# hub75d.net
KiCad netlist of a schematic drawn in Altium Designer
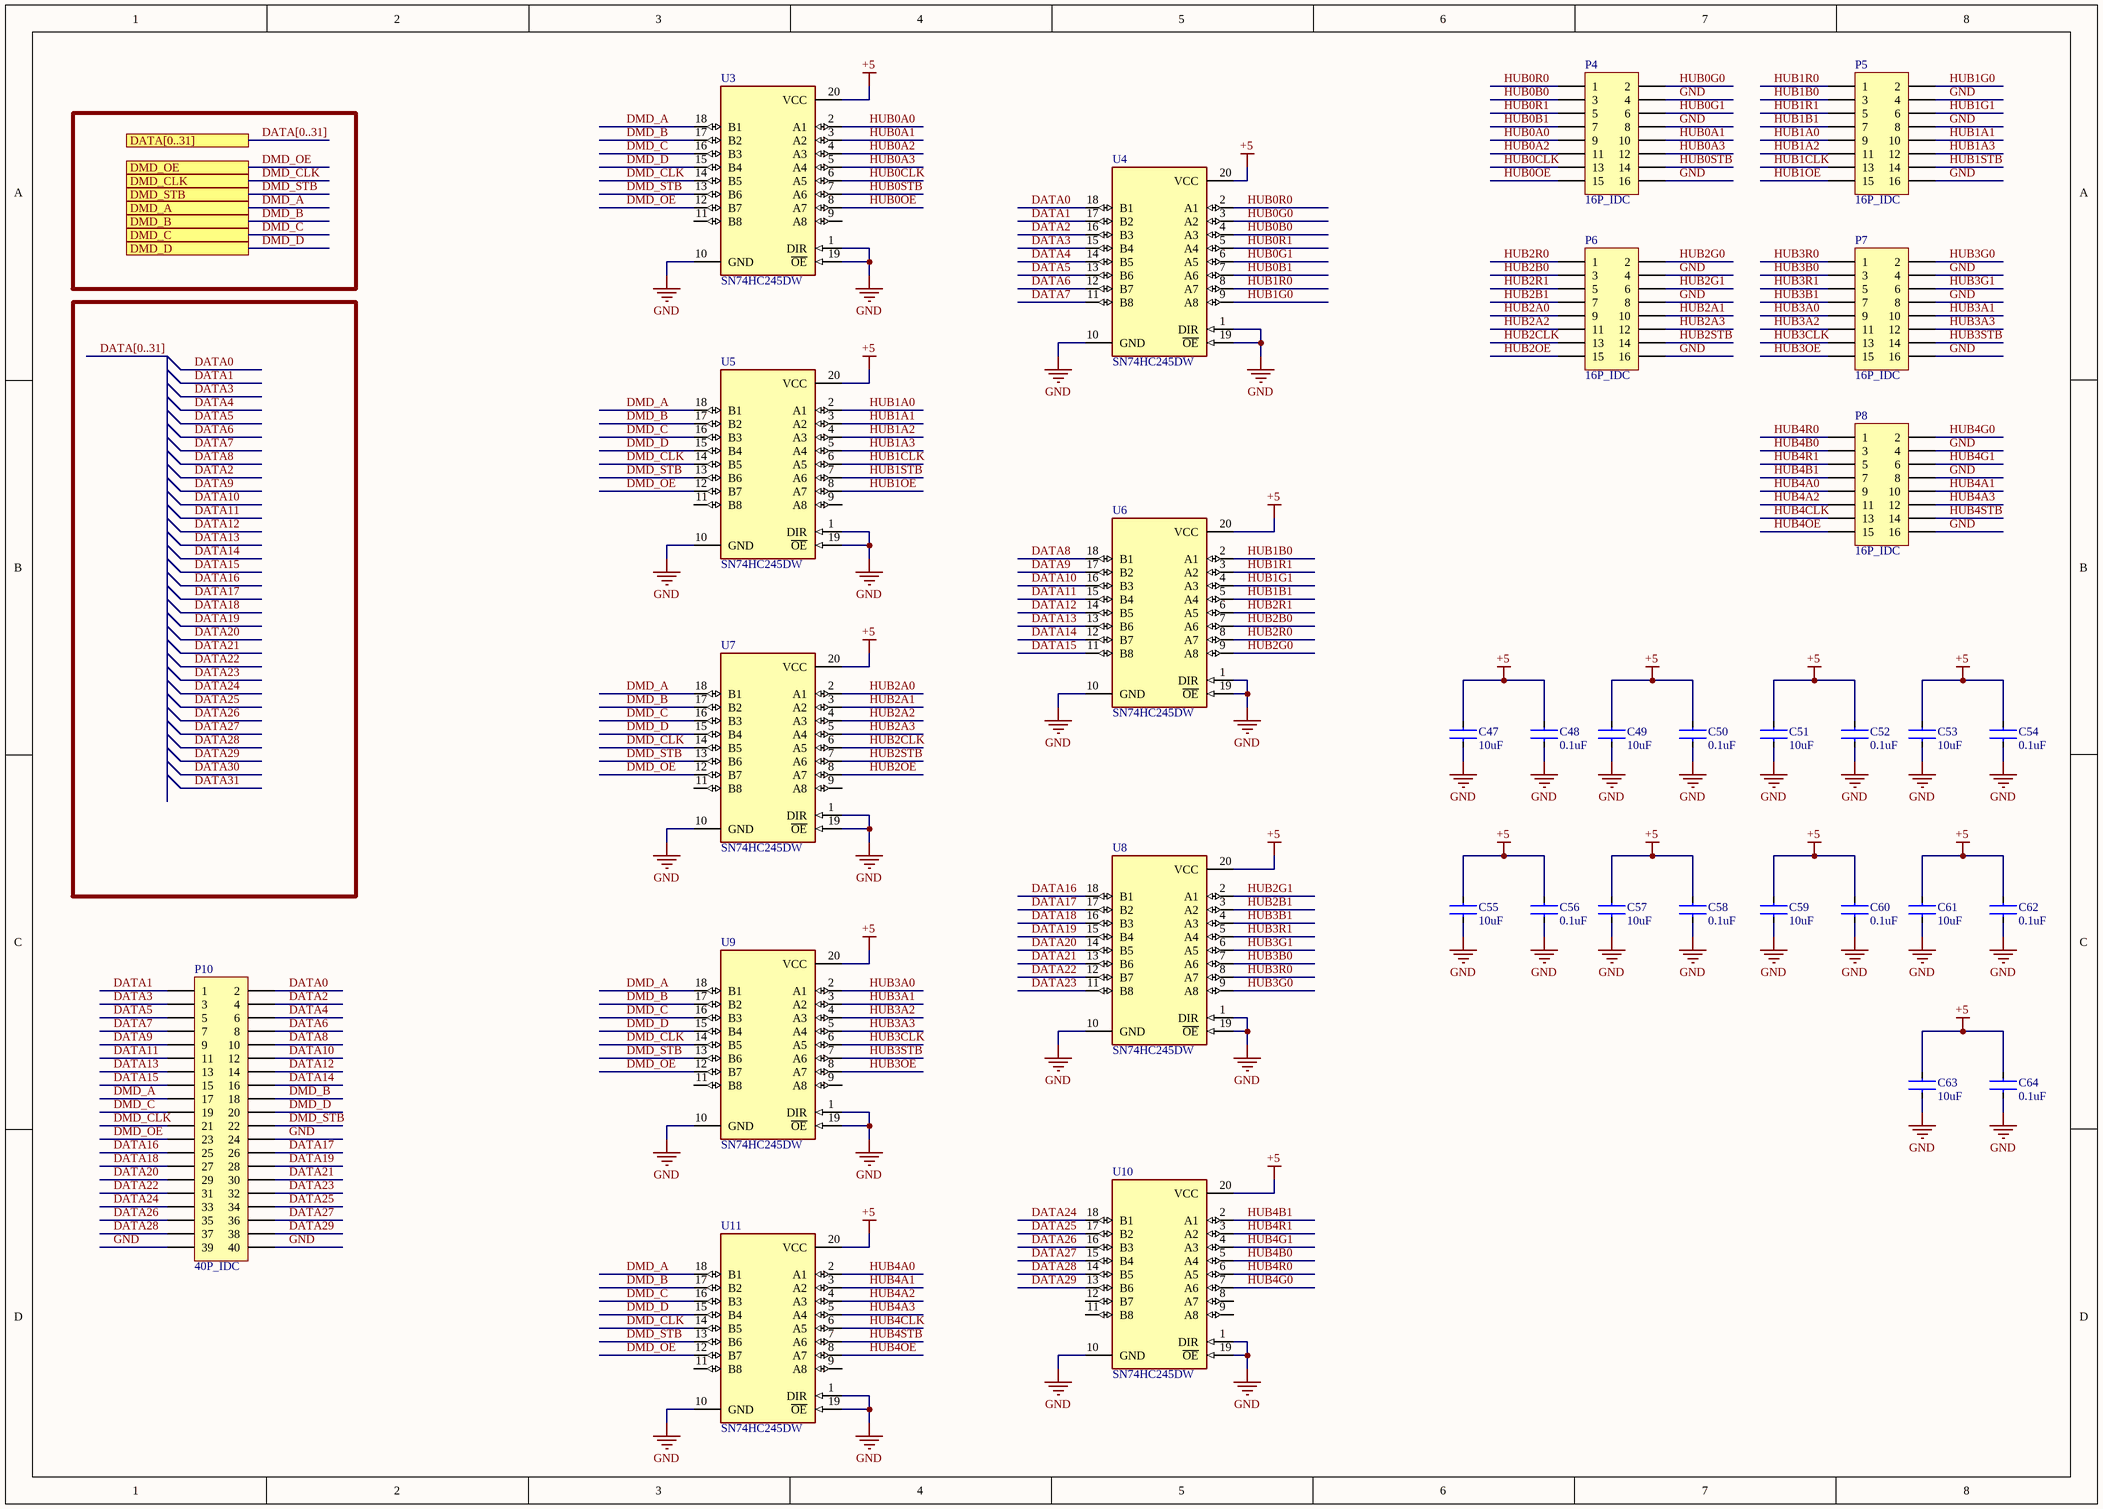
[diagram p0: hub75d.SchDoc]

(export (version "E")
  (design (tool "Eeschema 10.0.6"))
  (components
    (comp (ref "C47")
      (value "10uF")
      (footprint "C0402")
      (description "Cap Ceramic 10uF 16V X7R 10% Pad SMD 1206 125°C T/R")
      (fields
        (field (name "MANUFACTURER") "Samsung")
        (field (name "MANUFACTURER PART NUMBER") "CL31B106KOHNNNE")
      )
      (libsource (lib "afra") (part "CL31B106KOHNNNE"))
    )
    (comp (ref "C48")
      (value "0.1uF")
      (footprint "C0402")
      (description "Ceramic capacitor SMD-1206 100nF /50V X7R# K +-10%, Samsung, RoHS")
      (fields
        (field (name "MANUFACTURER") "Samsung")
        (field (name "MANUFACTURER PART NUMBER") "CL31B104KBCNNNC")
      )
      (libsource (lib "afra") (part "CL31B104KBCNNNC"))
    )
    (comp (ref "C49")
      (value "10uF")
      (footprint "C0402")
      (description "Cap Ceramic 10uF 16V X7R 10% Pad SMD 1206 125°C T/R")
      (fields
        (field (name "MANUFACTURER") "Samsung")
        (field (name "MANUFACTURER PART NUMBER") "CL31B106KOHNNNE")
      )
      (libsource (lib "afra") (part "CL31B106KOHNNNE"))
    )
    (comp (ref "C50")
      (value "0.1uF")
      (footprint "C0402")
      (description "Ceramic capacitor SMD-1206 100nF /50V X7R# K +-10%, Samsung, RoHS")
      (fields
        (field (name "MANUFACTURER") "Samsung")
        (field (name "MANUFACTURER PART NUMBER") "CL31B104KBCNNNC")
      )
      (libsource (lib "afra") (part "CL31B104KBCNNNC"))
    )
    (comp (ref "C51")
      (value "10uF")
      (footprint "C0402")
      (description "Cap Ceramic 10uF 16V X7R 10% Pad SMD 1206 125°C T/R")
      (fields
        (field (name "MANUFACTURER") "Samsung")
        (field (name "MANUFACTURER PART NUMBER") "CL31B106KOHNNNE")
      )
      (libsource (lib "afra") (part "CL31B106KOHNNNE"))
    )
    (comp (ref "C52")
      (value "0.1uF")
      (footprint "C0402")
      (description "Ceramic capacitor SMD-1206 100nF /50V X7R# K +-10%, Samsung, RoHS")
      (fields
        (field (name "MANUFACTURER") "Samsung")
        (field (name "MANUFACTURER PART NUMBER") "CL31B104KBCNNNC")
      )
      (libsource (lib "afra") (part "CL31B104KBCNNNC"))
    )
    (comp (ref "C53")
      (value "10uF")
      (footprint "C0402")
      (description "Cap Ceramic 10uF 16V X7R 10% Pad SMD 1206 125°C T/R")
      (fields
        (field (name "MANUFACTURER") "Samsung")
        (field (name "MANUFACTURER PART NUMBER") "CL31B106KOHNNNE")
      )
      (libsource (lib "afra") (part "CL31B106KOHNNNE"))
    )
    (comp (ref "C54")
      (value "0.1uF")
      (footprint "C0402")
      (description "Ceramic capacitor SMD-1206 100nF /50V X7R# K +-10%, Samsung, RoHS")
      (fields
        (field (name "MANUFACTURER") "Samsung")
        (field (name "MANUFACTURER PART NUMBER") "CL31B104KBCNNNC")
      )
      (libsource (lib "afra") (part "CL31B104KBCNNNC"))
    )
    (comp (ref "C55")
      (value "10uF")
      (footprint "C0402")
      (description "Cap Ceramic 10uF 16V X7R 10% Pad SMD 1206 125°C T/R")
      (fields
        (field (name "MANUFACTURER") "Samsung")
        (field (name "MANUFACTURER PART NUMBER") "CL31B106KOHNNNE")
      )
      (libsource (lib "afra") (part "CL31B106KOHNNNE"))
    )
    (comp (ref "C56")
      (value "0.1uF")
      (footprint "C0402")
      (description "Ceramic capacitor SMD-1206 100nF /50V X7R# K +-10%, Samsung, RoHS")
      (fields
        (field (name "MANUFACTURER") "Samsung")
        (field (name "MANUFACTURER PART NUMBER") "CL31B104KBCNNNC")
      )
      (libsource (lib "afra") (part "CL31B104KBCNNNC"))
    )
    (comp (ref "C57")
      (value "10uF")
      (footprint "C0402")
      (description "Cap Ceramic 10uF 16V X7R 10% Pad SMD 1206 125°C T/R")
      (fields
        (field (name "MANUFACTURER") "Samsung")
        (field (name "MANUFACTURER PART NUMBER") "CL31B106KOHNNNE")
      )
      (libsource (lib "afra") (part "CL31B106KOHNNNE"))
    )
    (comp (ref "C58")
      (value "0.1uF")
      (footprint "C0402")
      (description "Ceramic capacitor SMD-1206 100nF /50V X7R# K +-10%, Samsung, RoHS")
      (fields
        (field (name "MANUFACTURER") "Samsung")
        (field (name "MANUFACTURER PART NUMBER") "CL31B104KBCNNNC")
      )
      (libsource (lib "afra") (part "CL31B104KBCNNNC"))
    )
    (comp (ref "C59")
      (value "10uF")
      (footprint "C0402")
      (description "Cap Ceramic 10uF 16V X7R 10% Pad SMD 1206 125°C T/R")
      (fields
        (field (name "MANUFACTURER") "Samsung")
        (field (name "MANUFACTURER PART NUMBER") "CL31B106KOHNNNE")
      )
      (libsource (lib "afra") (part "CL31B106KOHNNNE"))
    )
    (comp (ref "C60")
      (value "0.1uF")
      (footprint "C0402")
      (description "Ceramic capacitor SMD-1206 100nF /50V X7R# K +-10%, Samsung, RoHS")
      (fields
        (field (name "MANUFACTURER") "Samsung")
        (field (name "MANUFACTURER PART NUMBER") "CL31B104KBCNNNC")
      )
      (libsource (lib "afra") (part "CL31B104KBCNNNC"))
    )
    (comp (ref "C61")
      (value "10uF")
      (footprint "C0402")
      (description "Cap Ceramic 10uF 16V X7R 10% Pad SMD 1206 125°C T/R")
      (fields
        (field (name "MANUFACTURER") "Samsung")
        (field (name "MANUFACTURER PART NUMBER") "CL31B106KOHNNNE")
      )
      (libsource (lib "afra") (part "CL31B106KOHNNNE"))
    )
    (comp (ref "C62")
      (value "0.1uF")
      (footprint "C0402")
      (description "Ceramic capacitor SMD-1206 100nF /50V X7R# K +-10%, Samsung, RoHS")
      (fields
        (field (name "MANUFACTURER") "Samsung")
        (field (name "MANUFACTURER PART NUMBER") "CL31B104KBCNNNC")
      )
      (libsource (lib "afra") (part "CL31B104KBCNNNC"))
    )
    (comp (ref "C63")
      (value "10uF")
      (footprint "C0402")
      (description "Cap Ceramic 10uF 16V X7R 10% Pad SMD 1206 125°C T/R")
      (fields
        (field (name "MANUFACTURER") "Samsung")
        (field (name "MANUFACTURER PART NUMBER") "CL31B106KOHNNNE")
      )
      (libsource (lib "afra") (part "CL31B106KOHNNNE"))
    )
    (comp (ref "C64")
      (value "0.1uF")
      (footprint "C0402")
      (description "Ceramic capacitor SMD-1206 100nF /50V X7R# K +-10%, Samsung, RoHS")
      (fields
        (field (name "MANUFACTURER") "Samsung")
        (field (name "MANUFACTURER PART NUMBER") "CL31B104KBCNNNC")
      )
      (libsource (lib "afra") (part "CL31B104KBCNNNC"))
    )
    (comp (ref "P4")
      (value "16P_IDC")
      (footprint "16Pin_IDC_Connector")
      (description "Headers & Wire Housings 16P STRAIGHT")
      (fields
        (field (name "MANUFACTURER") "Adam Equipment")
        (field (name "MANUFACTURER PART NUMBER") "BHR-16-VUA")
      )
      (libsource (lib "afra") (part "BHR-16-VUA"))
    )
    (comp (ref "P5")
      (value "16P_IDC")
      (footprint "16Pin_IDC_Connector")
      (description "Headers & Wire Housings 16P STRAIGHT")
      (fields
        (field (name "MANUFACTURER") "Adam Equipment")
        (field (name "MANUFACTURER PART NUMBER") "BHR-16-VUA")
      )
      (libsource (lib "afra") (part "BHR-16-VUA"))
    )
    (comp (ref "P6")
      (value "16P_IDC")
      (footprint "16Pin_IDC_Connector")
      (description "Headers & Wire Housings 16P STRAIGHT")
      (fields
        (field (name "MANUFACTURER") "Adam Equipment")
        (field (name "MANUFACTURER PART NUMBER") "BHR-16-VUA")
      )
      (libsource (lib "afra") (part "BHR-16-VUA"))
    )
    (comp (ref "P7")
      (value "16P_IDC")
      (footprint "16Pin_IDC_Connector")
      (description "Headers & Wire Housings 16P STRAIGHT")
      (fields
        (field (name "MANUFACTURER") "Adam Equipment")
        (field (name "MANUFACTURER PART NUMBER") "BHR-16-VUA")
      )
      (libsource (lib "afra") (part "BHR-16-VUA"))
    )
    (comp (ref "P8")
      (value "16P_IDC")
      (footprint "16Pin_IDC_Connector")
      (description "Headers & Wire Housings 16P STRAIGHT")
      (fields
        (field (name "MANUFACTURER") "Adam Equipment")
        (field (name "MANUFACTURER PART NUMBER") "BHR-16-VUA")
      )
      (libsource (lib "afra") (part "BHR-16-VUA"))
    )
    (comp (ref "P10")
      (value "40P_IDC")
      (footprint "40Pin_IDC_Connector")
      (description "Conn Shrouded Header (4 Sides) HDR 40 POS 2.54mm Solder ST Top Entry Thru-Hole Tray")
      (fields
        (field (name "MANUFACTURER") "Adam Equipment")
        (field (name "MANUFACTURER PART NUMBER") "BHR-20-VUA")
      )
      (libsource (lib "afra") (part "BHR-40-VUA"))
    )
    (comp (ref "U3")
      (value "SN74HC245DW")
      (footprint "DB20")
      (description "Transceiver, Non-Inverting 1 Element 8 Bit per Element Push-Pull Output 20-SOIC")
      (fields (field (name "MANUFACTURER") "Texas Instruments"))
      (libsource (lib "afra") (part "SN74HC245DW"))
    )
    (comp (ref "U4")
      (value "SN74HC245DW")
      (footprint "DB20")
      (description "Transceiver, Non-Inverting 1 Element 8 Bit per Element Push-Pull Output 20-SOIC")
      (fields (field (name "MANUFACTURER") "Texas Instruments"))
      (libsource (lib "afra") (part "SN74HC245DW"))
    )
    (comp (ref "U5")
      (value "SN74HC245DW")
      (footprint "DB20")
      (description "Transceiver, Non-Inverting 1 Element 8 Bit per Element Push-Pull Output 20-SOIC")
      (fields (field (name "MANUFACTURER") "Texas Instruments"))
      (libsource (lib "afra") (part "SN74HC245DW"))
    )
    (comp (ref "U6")
      (value "SN74HC245DW")
      (footprint "DB20")
      (description "Transceiver, Non-Inverting 1 Element 8 Bit per Element Push-Pull Output 20-SOIC")
      (fields (field (name "MANUFACTURER") "Texas Instruments"))
      (libsource (lib "afra") (part "SN74HC245DW"))
    )
    (comp (ref "U7")
      (value "SN74HC245DW")
      (footprint "DB20")
      (description "Transceiver, Non-Inverting 1 Element 8 Bit per Element Push-Pull Output 20-SOIC")
      (fields (field (name "MANUFACTURER") "Texas Instruments"))
      (libsource (lib "afra") (part "SN74HC245DW"))
    )
    (comp (ref "U8")
      (value "SN74HC245DW")
      (footprint "DB20")
      (description "Transceiver, Non-Inverting 1 Element 8 Bit per Element Push-Pull Output 20-SOIC")
      (fields (field (name "MANUFACTURER") "Texas Instruments"))
      (libsource (lib "afra") (part "SN74HC245DW"))
    )
    (comp (ref "U9")
      (value "SN74HC245DW")
      (footprint "DB20")
      (description "Transceiver, Non-Inverting 1 Element 8 Bit per Element Push-Pull Output 20-SOIC")
      (fields (field (name "MANUFACTURER") "Texas Instruments"))
      (libsource (lib "afra") (part "SN74HC245DW"))
    )
    (comp (ref "U10")
      (value "SN74HC245DW")
      (footprint "DB20")
      (description "Transceiver, Non-Inverting 1 Element 8 Bit per Element Push-Pull Output 20-SOIC")
      (fields (field (name "MANUFACTURER") "Texas Instruments"))
      (libsource (lib "afra") (part "SN74HC245DW"))
    )
    (comp (ref "U11")
      (value "SN74HC245DW")
      (footprint "DB20")
      (description "Transceiver, Non-Inverting 1 Element 8 Bit per Element Push-Pull Output 20-SOIC")
      (fields (field (name "MANUFACTURER") "Texas Instruments"))
      (libsource (lib "afra") (part "SN74HC245DW"))
    )
  )
  (nets
    (net (code "1") (name "+5") (class "Default")
      (node (ref "C47") (pin "1") (pinfunction "1_1") (pintype "passive"))
      (node (ref "C48") (pin "1") (pinfunction "1_1") (pintype "passive"))
      (node (ref "C49") (pin "1") (pinfunction "1_1") (pintype "passive"))
      (node (ref "C50") (pin "1") (pinfunction "1_1") (pintype "passive"))
      (node (ref "C51") (pin "1") (pinfunction "1_1") (pintype "passive"))
      (node (ref "C52") (pin "1") (pinfunction "1_1") (pintype "passive"))
      (node (ref "C53") (pin "1") (pinfunction "1_1") (pintype "passive"))
      (node (ref "C54") (pin "1") (pinfunction "1_1") (pintype "passive"))
      (node (ref "C55") (pin "1") (pinfunction "1_1") (pintype "passive"))
      (node (ref "C56") (pin "1") (pinfunction "1_1") (pintype "passive"))
      (node (ref "C57") (pin "1") (pinfunction "1_1") (pintype "passive"))
      (node (ref "C58") (pin "1") (pinfunction "1_1") (pintype "passive"))
      (node (ref "C59") (pin "1") (pinfunction "1_1") (pintype "passive"))
      (node (ref "C60") (pin "1") (pinfunction "1_1") (pintype "passive"))
      (node (ref "C61") (pin "1") (pinfunction "1_1") (pintype "passive"))
      (node (ref "C62") (pin "1") (pinfunction "1_1") (pintype "passive"))
      (node (ref "C63") (pin "1") (pinfunction "1_1") (pintype "passive"))
      (node (ref "C64") (pin "1") (pinfunction "1_1") (pintype "passive"))
      (node (ref "U10") (pin "20") (pinfunction "VCC_20") (pintype "power_in"))
      (node (ref "U11") (pin "20") (pinfunction "VCC_20") (pintype "power_in"))
      (node (ref "U3") (pin "20") (pinfunction "VCC_20") (pintype "power_in"))
      (node (ref "U4") (pin "20") (pinfunction "VCC_20") (pintype "power_in"))
      (node (ref "U5") (pin "20") (pinfunction "VCC_20") (pintype "power_in"))
      (node (ref "U6") (pin "20") (pinfunction "VCC_20") (pintype "power_in"))
      (node (ref "U7") (pin "20") (pinfunction "VCC_20") (pintype "power_in"))
      (node (ref "U8") (pin "20") (pinfunction "VCC_20") (pintype "power_in"))
      (node (ref "U9") (pin "20") (pinfunction "VCC_20") (pintype "power_in"))
    )
    (net (code "2") (name "/DATA0") (class "Default")
      (node (ref "P10") (pin "2") (pinfunction "2_2") (pintype "passive"))
      (node (ref "U4") (pin "18") (pinfunction "B1_18") (pintype "bidirectional"))
    )
    (net (code "3") (name "/DATA1") (class "Default")
      (node (ref "P10") (pin "1") (pinfunction "1_1") (pintype "passive"))
      (node (ref "U4") (pin "17") (pinfunction "B2_17") (pintype "bidirectional"))
    )
    (net (code "4") (name "/DATA2") (class "Default")
      (node (ref "P10") (pin "4") (pinfunction "4_4") (pintype "passive"))
      (node (ref "U4") (pin "16") (pinfunction "B3_16") (pintype "bidirectional"))
    )
    (net (code "5") (name "/DATA3") (class "Default")
      (node (ref "P10") (pin "3") (pinfunction "3_3") (pintype "passive"))
      (node (ref "U4") (pin "15") (pinfunction "B4_15") (pintype "bidirectional"))
    )
    (net (code "6") (name "/DATA4") (class "Default")
      (node (ref "P10") (pin "6") (pinfunction "6_6") (pintype "passive"))
      (node (ref "U4") (pin "14") (pinfunction "B5_14") (pintype "bidirectional"))
    )
    (net (code "7") (name "/DATA5") (class "Default")
      (node (ref "P10") (pin "5") (pinfunction "5_5") (pintype "passive"))
      (node (ref "U4") (pin "13") (pinfunction "B6_13") (pintype "bidirectional"))
    )
    (net (code "8") (name "/DATA6") (class "Default")
      (node (ref "P10") (pin "8") (pinfunction "8_8") (pintype "passive"))
      (node (ref "U4") (pin "12") (pinfunction "B7_12") (pintype "bidirectional"))
    )
    (net (code "9") (name "/DATA7") (class "Default")
      (node (ref "P10") (pin "7") (pinfunction "7_7") (pintype "passive"))
      (node (ref "U4") (pin "11") (pinfunction "B8_11") (pintype "bidirectional"))
    )
    (net (code "10") (name "/DATA8") (class "Default")
      (node (ref "P10") (pin "10") (pinfunction "10_10") (pintype "passive"))
      (node (ref "U6") (pin "18") (pinfunction "B1_18") (pintype "bidirectional"))
    )
    (net (code "11") (name "/DATA9") (class "Default")
      (node (ref "P10") (pin "9") (pinfunction "9_9") (pintype "passive"))
      (node (ref "U6") (pin "17") (pinfunction "B2_17") (pintype "bidirectional"))
    )
    (net (code "12") (name "/DATA10") (class "Default")
      (node (ref "P10") (pin "12") (pinfunction "12_12") (pintype "passive"))
      (node (ref "U6") (pin "16") (pinfunction "B3_16") (pintype "bidirectional"))
    )
    (net (code "13") (name "/DATA11") (class "Default")
      (node (ref "P10") (pin "11") (pinfunction "11_11") (pintype "passive"))
      (node (ref "U6") (pin "15") (pinfunction "B4_15") (pintype "bidirectional"))
    )
    (net (code "14") (name "/DATA12") (class "Default")
      (node (ref "P10") (pin "14") (pinfunction "14_14") (pintype "passive"))
      (node (ref "U6") (pin "14") (pinfunction "B5_14") (pintype "bidirectional"))
    )
    (net (code "15") (name "/DATA13") (class "Default")
      (node (ref "P10") (pin "13") (pinfunction "13_13") (pintype "passive"))
      (node (ref "U6") (pin "13") (pinfunction "B6_13") (pintype "bidirectional"))
    )
    (net (code "16") (name "/DATA14") (class "Default")
      (node (ref "P10") (pin "16") (pinfunction "16_16") (pintype "passive"))
      (node (ref "U6") (pin "12") (pinfunction "B7_12") (pintype "bidirectional"))
    )
    (net (code "17") (name "/DATA15") (class "Default")
      (node (ref "P10") (pin "15") (pinfunction "15_15") (pintype "passive"))
      (node (ref "U6") (pin "11") (pinfunction "B8_11") (pintype "bidirectional"))
    )
    (net (code "18") (name "/DATA16") (class "Default")
      (node (ref "P10") (pin "25") (pinfunction "25_25") (pintype "passive"))
      (node (ref "U8") (pin "18") (pinfunction "B1_18") (pintype "bidirectional"))
    )
    (net (code "19") (name "/DATA17") (class "Default")
      (node (ref "P10") (pin "26") (pinfunction "26_26") (pintype "passive"))
      (node (ref "U8") (pin "17") (pinfunction "B2_17") (pintype "bidirectional"))
    )
    (net (code "20") (name "/DATA18") (class "Default")
      (node (ref "P10") (pin "27") (pinfunction "27_27") (pintype "passive"))
      (node (ref "U8") (pin "16") (pinfunction "B3_16") (pintype "bidirectional"))
    )
    (net (code "21") (name "/DATA19") (class "Default")
      (node (ref "P10") (pin "28") (pinfunction "28_28") (pintype "passive"))
      (node (ref "U8") (pin "15") (pinfunction "B4_15") (pintype "bidirectional"))
    )
    (net (code "22") (name "/DATA20") (class "Default")
      (node (ref "P10") (pin "29") (pinfunction "29_29") (pintype "passive"))
      (node (ref "U8") (pin "14") (pinfunction "B5_14") (pintype "bidirectional"))
    )
    (net (code "23") (name "/DATA21") (class "Default")
      (node (ref "P10") (pin "30") (pinfunction "30_30") (pintype "passive"))
      (node (ref "U8") (pin "13") (pinfunction "B6_13") (pintype "bidirectional"))
    )
    (net (code "24") (name "/DATA22") (class "Default")
      (node (ref "P10") (pin "31") (pinfunction "31_31") (pintype "passive"))
      (node (ref "U8") (pin "12") (pinfunction "B7_12") (pintype "bidirectional"))
    )
    (net (code "25") (name "/DATA23") (class "Default")
      (node (ref "P10") (pin "32") (pinfunction "32_32") (pintype "passive"))
      (node (ref "U8") (pin "11") (pinfunction "B8_11") (pintype "bidirectional"))
    )
    (net (code "26") (name "/DATA24") (class "Default")
      (node (ref "P10") (pin "33") (pinfunction "33_33") (pintype "passive"))
      (node (ref "U10") (pin "18") (pinfunction "B1_18") (pintype "bidirectional"))
    )
    (net (code "27") (name "/DATA25") (class "Default")
      (node (ref "P10") (pin "34") (pinfunction "34_34") (pintype "passive"))
      (node (ref "U10") (pin "17") (pinfunction "B2_17") (pintype "bidirectional"))
    )
    (net (code "28") (name "/DATA26") (class "Default")
      (node (ref "P10") (pin "35") (pinfunction "35_35") (pintype "passive"))
      (node (ref "U10") (pin "16") (pinfunction "B3_16") (pintype "bidirectional"))
    )
    (net (code "29") (name "/DATA27") (class "Default")
      (node (ref "P10") (pin "36") (pinfunction "36_36") (pintype "passive"))
      (node (ref "U10") (pin "15") (pinfunction "B4_15") (pintype "bidirectional"))
    )
    (net (code "30") (name "/DATA28") (class "Default")
      (node (ref "P10") (pin "37") (pinfunction "37_37") (pintype "passive"))
      (node (ref "U10") (pin "14") (pinfunction "B5_14") (pintype "bidirectional"))
    )
    (net (code "31") (name "/DATA29") (class "Default")
      (node (ref "P10") (pin "38") (pinfunction "38_38") (pintype "passive"))
      (node (ref "U10") (pin "13") (pinfunction "B6_13") (pintype "bidirectional"))
    )
    (net (code "35") (name "/DMD_A") (class "Default")
      (node (ref "P10") (pin "17") (pinfunction "17_17") (pintype "passive"))
      (node (ref "U11") (pin "18") (pinfunction "B1_18") (pintype "bidirectional"))
      (node (ref "U3") (pin "18") (pinfunction "B1_18") (pintype "bidirectional"))
      (node (ref "U5") (pin "18") (pinfunction "B1_18") (pintype "bidirectional"))
      (node (ref "U7") (pin "18") (pinfunction "B1_18") (pintype "bidirectional"))
      (node (ref "U9") (pin "18") (pinfunction "B1_18") (pintype "bidirectional"))
    )
    (net (code "36") (name "/DMD_B") (class "Default")
      (node (ref "P10") (pin "18") (pinfunction "18_18") (pintype "passive"))
      (node (ref "U11") (pin "17") (pinfunction "B2_17") (pintype "bidirectional"))
      (node (ref "U3") (pin "17") (pinfunction "B2_17") (pintype "bidirectional"))
      (node (ref "U5") (pin "17") (pinfunction "B2_17") (pintype "bidirectional"))
      (node (ref "U7") (pin "17") (pinfunction "B2_17") (pintype "bidirectional"))
      (node (ref "U9") (pin "17") (pinfunction "B2_17") (pintype "bidirectional"))
    )
    (net (code "37") (name "/DMD_C") (class "Default")
      (node (ref "P10") (pin "19") (pinfunction "19_19") (pintype "passive"))
      (node (ref "U11") (pin "16") (pinfunction "B3_16") (pintype "bidirectional"))
      (node (ref "U3") (pin "16") (pinfunction "B3_16") (pintype "bidirectional"))
      (node (ref "U5") (pin "16") (pinfunction "B3_16") (pintype "bidirectional"))
      (node (ref "U7") (pin "16") (pinfunction "B3_16") (pintype "bidirectional"))
      (node (ref "U9") (pin "16") (pinfunction "B3_16") (pintype "bidirectional"))
    )
    (net (code "38") (name "/DMD_CLK") (class "Default")
      (node (ref "P10") (pin "21") (pinfunction "21_21") (pintype "passive"))
      (node (ref "U11") (pin "14") (pinfunction "B5_14") (pintype "bidirectional"))
      (node (ref "U3") (pin "14") (pinfunction "B5_14") (pintype "bidirectional"))
      (node (ref "U5") (pin "14") (pinfunction "B5_14") (pintype "bidirectional"))
      (node (ref "U7") (pin "14") (pinfunction "B5_14") (pintype "bidirectional"))
      (node (ref "U9") (pin "14") (pinfunction "B5_14") (pintype "bidirectional"))
    )
    (net (code "39") (name "/DMD_D") (class "Default")
      (node (ref "P10") (pin "20") (pinfunction "20_20") (pintype "passive"))
      (node (ref "U11") (pin "15") (pinfunction "B4_15") (pintype "bidirectional"))
      (node (ref "U3") (pin "15") (pinfunction "B4_15") (pintype "bidirectional"))
      (node (ref "U5") (pin "15") (pinfunction "B4_15") (pintype "bidirectional"))
      (node (ref "U7") (pin "15") (pinfunction "B4_15") (pintype "bidirectional"))
      (node (ref "U9") (pin "15") (pinfunction "B4_15") (pintype "bidirectional"))
    )
    (net (code "40") (name "/DMD_OE") (class "Default")
      (node (ref "P10") (pin "23") (pinfunction "23_23") (pintype "passive"))
      (node (ref "U11") (pin "12") (pinfunction "B7_12") (pintype "bidirectional"))
      (node (ref "U3") (pin "12") (pinfunction "B7_12") (pintype "bidirectional"))
      (node (ref "U5") (pin "12") (pinfunction "B7_12") (pintype "bidirectional"))
      (node (ref "U7") (pin "12") (pinfunction "B7_12") (pintype "bidirectional"))
      (node (ref "U9") (pin "12") (pinfunction "B7_12") (pintype "bidirectional"))
    )
    (net (code "41") (name "/DMD_STB") (class "Default")
      (node (ref "P10") (pin "22") (pinfunction "22_22") (pintype "passive"))
      (node (ref "U11") (pin "13") (pinfunction "B6_13") (pintype "bidirectional"))
      (node (ref "U3") (pin "13") (pinfunction "B6_13") (pintype "bidirectional"))
      (node (ref "U5") (pin "13") (pinfunction "B6_13") (pintype "bidirectional"))
      (node (ref "U7") (pin "13") (pinfunction "B6_13") (pintype "bidirectional"))
      (node (ref "U9") (pin "13") (pinfunction "B6_13") (pintype "bidirectional"))
    )
    (net (code "42") (name "/HUB0A0") (class "Default")
      (node (ref "P4") (pin "9") (pinfunction "9_9") (pintype "passive"))
      (node (ref "U3") (pin "2") (pinfunction "A1_2") (pintype "bidirectional"))
    )
    (net (code "43") (name "/HUB0A1") (class "Default")
      (node (ref "P4") (pin "10") (pinfunction "10_10") (pintype "passive"))
      (node (ref "U3") (pin "3") (pinfunction "A2_3") (pintype "bidirectional"))
    )
    (net (code "44") (name "/HUB0A2") (class "Default")
      (node (ref "P4") (pin "11") (pinfunction "11_11") (pintype "passive"))
      (node (ref "U3") (pin "4") (pinfunction "A3_4") (pintype "bidirectional"))
    )
    (net (code "45") (name "/HUB0A3") (class "Default")
      (node (ref "P4") (pin "12") (pinfunction "12_12") (pintype "passive"))
      (node (ref "U3") (pin "5") (pinfunction "A4_5") (pintype "bidirectional"))
    )
    (net (code "46") (name "/HUB0B0") (class "Default")
      (node (ref "P4") (pin "3") (pinfunction "3_3") (pintype "passive"))
      (node (ref "U4") (pin "4") (pinfunction "A3_4") (pintype "bidirectional"))
    )
    (net (code "47") (name "/HUB0B1") (class "Default")
      (node (ref "P4") (pin "7") (pinfunction "7_7") (pintype "passive"))
      (node (ref "U4") (pin "7") (pinfunction "A6_7") (pintype "bidirectional"))
    )
    (net (code "48") (name "/HUB0CLK") (class "Default")
      (node (ref "P4") (pin "13") (pinfunction "13_13") (pintype "passive"))
      (node (ref "U3") (pin "6") (pinfunction "A5_6") (pintype "bidirectional"))
    )
    (net (code "49") (name "/HUB0G0") (class "Default")
      (node (ref "P4") (pin "2") (pinfunction "2_2") (pintype "passive"))
      (node (ref "U4") (pin "3") (pinfunction "A2_3") (pintype "bidirectional"))
    )
    (net (code "50") (name "/HUB0G1") (class "Default")
      (node (ref "P4") (pin "6") (pinfunction "6_6") (pintype "passive"))
      (node (ref "U4") (pin "6") (pinfunction "A5_6") (pintype "bidirectional"))
    )
    (net (code "51") (name "/HUB0OE") (class "Default")
      (node (ref "P4") (pin "15") (pinfunction "15_15") (pintype "passive"))
      (node (ref "U3") (pin "8") (pinfunction "A7_8") (pintype "bidirectional"))
    )
    (net (code "52") (name "/HUB0R0") (class "Default")
      (node (ref "P4") (pin "1") (pinfunction "1_1") (pintype "passive"))
      (node (ref "U4") (pin "2") (pinfunction "A1_2") (pintype "bidirectional"))
    )
    (net (code "53") (name "/HUB0R1") (class "Default")
      (node (ref "P4") (pin "5") (pinfunction "5_5") (pintype "passive"))
      (node (ref "U4") (pin "5") (pinfunction "A4_5") (pintype "bidirectional"))
    )
    (net (code "54") (name "/HUB0STB") (class "Default")
      (node (ref "P4") (pin "14") (pinfunction "14_14") (pintype "passive"))
      (node (ref "U3") (pin "7") (pinfunction "A6_7") (pintype "bidirectional"))
    )
    (net (code "55") (name "/HUB1A0") (class "Default")
      (node (ref "P5") (pin "9") (pinfunction "9_9") (pintype "passive"))
      (node (ref "U5") (pin "2") (pinfunction "A1_2") (pintype "bidirectional"))
    )
    (net (code "56") (name "/HUB1A1") (class "Default")
      (node (ref "P5") (pin "10") (pinfunction "10_10") (pintype "passive"))
      (node (ref "U5") (pin "3") (pinfunction "A2_3") (pintype "bidirectional"))
    )
    (net (code "57") (name "/HUB1A2") (class "Default")
      (node (ref "P5") (pin "11") (pinfunction "11_11") (pintype "passive"))
      (node (ref "U5") (pin "4") (pinfunction "A3_4") (pintype "bidirectional"))
    )
    (net (code "58") (name "/HUB1A3") (class "Default")
      (node (ref "P5") (pin "12") (pinfunction "12_12") (pintype "passive"))
      (node (ref "U5") (pin "5") (pinfunction "A4_5") (pintype "bidirectional"))
    )
    (net (code "59") (name "/HUB1B0") (class "Default")
      (node (ref "P5") (pin "3") (pinfunction "3_3") (pintype "passive"))
      (node (ref "U6") (pin "2") (pinfunction "A1_2") (pintype "bidirectional"))
    )
    (net (code "60") (name "/HUB1B1") (class "Default")
      (node (ref "P5") (pin "7") (pinfunction "7_7") (pintype "passive"))
      (node (ref "U6") (pin "5") (pinfunction "A4_5") (pintype "bidirectional"))
    )
    (net (code "61") (name "/HUB1CLK") (class "Default")
      (node (ref "P5") (pin "13") (pinfunction "13_13") (pintype "passive"))
      (node (ref "U5") (pin "6") (pinfunction "A5_6") (pintype "bidirectional"))
    )
    (net (code "62") (name "/HUB1G0") (class "Default")
      (node (ref "P5") (pin "2") (pinfunction "2_2") (pintype "passive"))
      (node (ref "U4") (pin "9") (pinfunction "A8_9") (pintype "bidirectional"))
    )
    (net (code "63") (name "/HUB1G1") (class "Default")
      (node (ref "P5") (pin "6") (pinfunction "6_6") (pintype "passive"))
      (node (ref "U6") (pin "4") (pinfunction "A3_4") (pintype "bidirectional"))
    )
    (net (code "64") (name "/HUB1OE") (class "Default")
      (node (ref "P5") (pin "15") (pinfunction "15_15") (pintype "passive"))
      (node (ref "U5") (pin "8") (pinfunction "A7_8") (pintype "bidirectional"))
    )
    (net (code "65") (name "/HUB1R0") (class "Default")
      (node (ref "P5") (pin "1") (pinfunction "1_1") (pintype "passive"))
      (node (ref "U4") (pin "8") (pinfunction "A7_8") (pintype "bidirectional"))
    )
    (net (code "66") (name "/HUB1R1") (class "Default")
      (node (ref "P5") (pin "5") (pinfunction "5_5") (pintype "passive"))
      (node (ref "U6") (pin "3") (pinfunction "A2_3") (pintype "bidirectional"))
    )
    (net (code "67") (name "/HUB1STB") (class "Default")
      (node (ref "P5") (pin "14") (pinfunction "14_14") (pintype "passive"))
      (node (ref "U5") (pin "7") (pinfunction "A6_7") (pintype "bidirectional"))
    )
    (net (code "68") (name "/HUB2A0") (class "Default")
      (node (ref "P6") (pin "9") (pinfunction "9_9") (pintype "passive"))
      (node (ref "U7") (pin "2") (pinfunction "A1_2") (pintype "bidirectional"))
    )
    (net (code "69") (name "/HUB2A1") (class "Default")
      (node (ref "P6") (pin "10") (pinfunction "10_10") (pintype "passive"))
      (node (ref "U7") (pin "3") (pinfunction "A2_3") (pintype "bidirectional"))
    )
    (net (code "70") (name "/HUB2A2") (class "Default")
      (node (ref "P6") (pin "11") (pinfunction "11_11") (pintype "passive"))
      (node (ref "U7") (pin "4") (pinfunction "A3_4") (pintype "bidirectional"))
    )
    (net (code "71") (name "/HUB2A3") (class "Default")
      (node (ref "P6") (pin "12") (pinfunction "12_12") (pintype "passive"))
      (node (ref "U7") (pin "5") (pinfunction "A4_5") (pintype "bidirectional"))
    )
    (net (code "72") (name "/HUB2B0") (class "Default")
      (node (ref "P6") (pin "3") (pinfunction "3_3") (pintype "passive"))
      (node (ref "U6") (pin "7") (pinfunction "A6_7") (pintype "bidirectional"))
    )
    (net (code "73") (name "/HUB2B1") (class "Default")
      (node (ref "P6") (pin "7") (pinfunction "7_7") (pintype "passive"))
      (node (ref "U8") (pin "3") (pinfunction "A2_3") (pintype "bidirectional"))
    )
    (net (code "74") (name "/HUB2CLK") (class "Default")
      (node (ref "P6") (pin "13") (pinfunction "13_13") (pintype "passive"))
      (node (ref "U7") (pin "6") (pinfunction "A5_6") (pintype "bidirectional"))
    )
    (net (code "75") (name "/HUB2G0") (class "Default")
      (node (ref "P6") (pin "2") (pinfunction "2_2") (pintype "passive"))
      (node (ref "U6") (pin "9") (pinfunction "A8_9") (pintype "bidirectional"))
    )
    (net (code "76") (name "/HUB2G1") (class "Default")
      (node (ref "P6") (pin "6") (pinfunction "6_6") (pintype "passive"))
      (node (ref "U8") (pin "2") (pinfunction "A1_2") (pintype "bidirectional"))
    )
    (net (code "77") (name "/HUB2OE") (class "Default")
      (node (ref "P6") (pin "15") (pinfunction "15_15") (pintype "passive"))
      (node (ref "U7") (pin "8") (pinfunction "A7_8") (pintype "bidirectional"))
    )
    (net (code "78") (name "/HUB2R0") (class "Default")
      (node (ref "P6") (pin "1") (pinfunction "1_1") (pintype "passive"))
      (node (ref "U6") (pin "8") (pinfunction "A7_8") (pintype "bidirectional"))
    )
    (net (code "79") (name "/HUB2R1") (class "Default")
      (node (ref "P6") (pin "5") (pinfunction "5_5") (pintype "passive"))
      (node (ref "U6") (pin "6") (pinfunction "A5_6") (pintype "bidirectional"))
    )
    (net (code "80") (name "/HUB2STB") (class "Default")
      (node (ref "P6") (pin "14") (pinfunction "14_14") (pintype "passive"))
      (node (ref "U7") (pin "7") (pinfunction "A6_7") (pintype "bidirectional"))
    )
    (net (code "81") (name "/HUB3A0") (class "Default")
      (node (ref "P7") (pin "9") (pinfunction "9_9") (pintype "passive"))
      (node (ref "U9") (pin "2") (pinfunction "A1_2") (pintype "bidirectional"))
    )
    (net (code "82") (name "/HUB3A1") (class "Default")
      (node (ref "P7") (pin "10") (pinfunction "10_10") (pintype "passive"))
      (node (ref "U9") (pin "3") (pinfunction "A2_3") (pintype "bidirectional"))
    )
    (net (code "83") (name "/HUB3A2") (class "Default")
      (node (ref "P7") (pin "11") (pinfunction "11_11") (pintype "passive"))
      (node (ref "U9") (pin "4") (pinfunction "A3_4") (pintype "bidirectional"))
    )
    (net (code "84") (name "/HUB3A3") (class "Default")
      (node (ref "P7") (pin "12") (pinfunction "12_12") (pintype "passive"))
      (node (ref "U9") (pin "5") (pinfunction "A4_5") (pintype "bidirectional"))
    )
    (net (code "85") (name "/HUB3B0") (class "Default")
      (node (ref "P7") (pin "3") (pinfunction "3_3") (pintype "passive"))
      (node (ref "U8") (pin "7") (pinfunction "A6_7") (pintype "bidirectional"))
    )
    (net (code "86") (name "/HUB3B1") (class "Default")
      (node (ref "P7") (pin "7") (pinfunction "7_7") (pintype "passive"))
      (node (ref "U8") (pin "4") (pinfunction "A3_4") (pintype "bidirectional"))
    )
    (net (code "87") (name "/HUB3CLK") (class "Default")
      (node (ref "P7") (pin "13") (pinfunction "13_13") (pintype "passive"))
      (node (ref "U9") (pin "6") (pinfunction "A5_6") (pintype "bidirectional"))
    )
    (net (code "88") (name "/HUB3G0") (class "Default")
      (node (ref "P7") (pin "2") (pinfunction "2_2") (pintype "passive"))
      (node (ref "U8") (pin "9") (pinfunction "A8_9") (pintype "bidirectional"))
    )
    (net (code "89") (name "/HUB3G1") (class "Default")
      (node (ref "P7") (pin "6") (pinfunction "6_6") (pintype "passive"))
      (node (ref "U8") (pin "6") (pinfunction "A5_6") (pintype "bidirectional"))
    )
    (net (code "90") (name "/HUB3OE") (class "Default")
      (node (ref "P7") (pin "15") (pinfunction "15_15") (pintype "passive"))
      (node (ref "U9") (pin "8") (pinfunction "A7_8") (pintype "bidirectional"))
    )
    (net (code "91") (name "/HUB3R0") (class "Default")
      (node (ref "P7") (pin "1") (pinfunction "1_1") (pintype "passive"))
      (node (ref "U8") (pin "8") (pinfunction "A7_8") (pintype "bidirectional"))
    )
    (net (code "92") (name "/HUB3R1") (class "Default")
      (node (ref "P7") (pin "5") (pinfunction "5_5") (pintype "passive"))
      (node (ref "U8") (pin "5") (pinfunction "A4_5") (pintype "bidirectional"))
    )
    (net (code "93") (name "/HUB3STB") (class "Default")
      (node (ref "P7") (pin "14") (pinfunction "14_14") (pintype "passive"))
      (node (ref "U9") (pin "7") (pinfunction "A6_7") (pintype "bidirectional"))
    )
    (net (code "94") (name "/HUB4A0") (class "Default")
      (node (ref "P8") (pin "9") (pinfunction "9_9") (pintype "passive"))
      (node (ref "U11") (pin "2") (pinfunction "A1_2") (pintype "bidirectional"))
    )
    (net (code "95") (name "/HUB4A1") (class "Default")
      (node (ref "P8") (pin "10") (pinfunction "10_10") (pintype "passive"))
      (node (ref "U11") (pin "3") (pinfunction "A2_3") (pintype "bidirectional"))
    )
    (net (code "96") (name "/HUB4A2") (class "Default")
      (node (ref "P8") (pin "11") (pinfunction "11_11") (pintype "passive"))
      (node (ref "U11") (pin "4") (pinfunction "A3_4") (pintype "bidirectional"))
    )
    (net (code "97") (name "/HUB4A3") (class "Default")
      (node (ref "P8") (pin "12") (pinfunction "12_12") (pintype "passive"))
      (node (ref "U11") (pin "5") (pinfunction "A4_5") (pintype "bidirectional"))
    )
    (net (code "98") (name "/HUB4B0") (class "Default")
      (node (ref "P8") (pin "3") (pinfunction "3_3") (pintype "passive"))
      (node (ref "U10") (pin "5") (pinfunction "A4_5") (pintype "bidirectional"))
    )
    (net (code "99") (name "/HUB4B1") (class "Default")
      (node (ref "P8") (pin "7") (pinfunction "7_7") (pintype "passive"))
      (node (ref "U10") (pin "2") (pinfunction "A1_2") (pintype "bidirectional"))
    )
    (net (code "100") (name "/HUB4CLK") (class "Default")
      (node (ref "P8") (pin "13") (pinfunction "13_13") (pintype "passive"))
      (node (ref "U11") (pin "6") (pinfunction "A5_6") (pintype "bidirectional"))
    )
    (net (code "101") (name "/HUB4G0") (class "Default")
      (node (ref "P8") (pin "2") (pinfunction "2_2") (pintype "passive"))
      (node (ref "U10") (pin "7") (pinfunction "A6_7") (pintype "bidirectional"))
    )
    (net (code "102") (name "/HUB4G1") (class "Default")
      (node (ref "P8") (pin "6") (pinfunction "6_6") (pintype "passive"))
      (node (ref "U10") (pin "4") (pinfunction "A3_4") (pintype "bidirectional"))
    )
    (net (code "103") (name "/HUB4OE") (class "Default")
      (node (ref "P8") (pin "15") (pinfunction "15_15") (pintype "passive"))
      (node (ref "U11") (pin "8") (pinfunction "A7_8") (pintype "bidirectional"))
    )
    (net (code "104") (name "/HUB4R0") (class "Default")
      (node (ref "P8") (pin "1") (pinfunction "1_1") (pintype "passive"))
      (node (ref "U10") (pin "6") (pinfunction "A5_6") (pintype "bidirectional"))
    )
    (net (code "105") (name "/HUB4R1") (class "Default")
      (node (ref "P8") (pin "5") (pinfunction "5_5") (pintype "passive"))
      (node (ref "U10") (pin "3") (pinfunction "A2_3") (pintype "bidirectional"))
    )
    (net (code "106") (name "/HUB4STB") (class "Default")
      (node (ref "P8") (pin "14") (pinfunction "14_14") (pintype "passive"))
      (node (ref "U11") (pin "7") (pinfunction "A6_7") (pintype "bidirectional"))
    )
    (net (code "107") (name "GND") (class "Default")
      (node (ref "C47") (pin "2") (pinfunction "2_2") (pintype "passive"))
      (node (ref "C48") (pin "2") (pinfunction "2_2") (pintype "passive"))
      (node (ref "C49") (pin "2") (pinfunction "2_2") (pintype "passive"))
      (node (ref "C50") (pin "2") (pinfunction "2_2") (pintype "passive"))
      (node (ref "C51") (pin "2") (pinfunction "2_2") (pintype "passive"))
      (node (ref "C52") (pin "2") (pinfunction "2_2") (pintype "passive"))
      (node (ref "C53") (pin "2") (pinfunction "2_2") (pintype "passive"))
      (node (ref "C54") (pin "2") (pinfunction "2_2") (pintype "passive"))
      (node (ref "C55") (pin "2") (pinfunction "2_2") (pintype "passive"))
      (node (ref "C56") (pin "2") (pinfunction "2_2") (pintype "passive"))
      (node (ref "C57") (pin "2") (pinfunction "2_2") (pintype "passive"))
      (node (ref "C58") (pin "2") (pinfunction "2_2") (pintype "passive"))
      (node (ref "C59") (pin "2") (pinfunction "2_2") (pintype "passive"))
      (node (ref "C60") (pin "2") (pinfunction "2_2") (pintype "passive"))
      (node (ref "C61") (pin "2") (pinfunction "2_2") (pintype "passive"))
      (node (ref "C62") (pin "2") (pinfunction "2_2") (pintype "passive"))
      (node (ref "C63") (pin "2") (pinfunction "2_2") (pintype "passive"))
      (node (ref "C64") (pin "2") (pinfunction "2_2") (pintype "passive"))
      (node (ref "P10") (pin "24") (pinfunction "24_24") (pintype "passive"))
      (node (ref "P10") (pin "39") (pinfunction "39_39") (pintype "passive"))
      (node (ref "P10") (pin "40") (pinfunction "40_40") (pintype "passive"))
      (node (ref "P4") (pin "16") (pinfunction "16_16") (pintype "passive"))
      (node (ref "P4") (pin "4") (pinfunction "4_4") (pintype "passive"))
      (node (ref "P4") (pin "8") (pinfunction "8_8") (pintype "passive"))
      (node (ref "P5") (pin "16") (pinfunction "16_16") (pintype "passive"))
      (node (ref "P5") (pin "4") (pinfunction "4_4") (pintype "passive"))
      (node (ref "P5") (pin "8") (pinfunction "8_8") (pintype "passive"))
      (node (ref "P6") (pin "16") (pinfunction "16_16") (pintype "passive"))
      (node (ref "P6") (pin "4") (pinfunction "4_4") (pintype "passive"))
      (node (ref "P6") (pin "8") (pinfunction "8_8") (pintype "passive"))
      (node (ref "P7") (pin "16") (pinfunction "16_16") (pintype "passive"))
      (node (ref "P7") (pin "4") (pinfunction "4_4") (pintype "passive"))
      (node (ref "P7") (pin "8") (pinfunction "8_8") (pintype "passive"))
      (node (ref "P8") (pin "16") (pinfunction "16_16") (pintype "passive"))
      (node (ref "P8") (pin "4") (pinfunction "4_4") (pintype "passive"))
      (node (ref "P8") (pin "8") (pinfunction "8_8") (pintype "passive"))
      (node (ref "U10") (pin "1") (pinfunction "DIR_1") (pintype "input"))
      (node (ref "U10") (pin "10") (pinfunction "GND_10") (pintype "power_in"))
      (node (ref "U10") (pin "19") (pinfunction "~{OE}_19") (pintype "input"))
      (node (ref "U11") (pin "1") (pinfunction "DIR_1") (pintype "input"))
      (node (ref "U11") (pin "10") (pinfunction "GND_10") (pintype "power_in"))
      (node (ref "U11") (pin "19") (pinfunction "~{OE}_19") (pintype "input"))
      (node (ref "U3") (pin "1") (pinfunction "DIR_1") (pintype "input"))
      (node (ref "U3") (pin "10") (pinfunction "GND_10") (pintype "power_in"))
      (node (ref "U3") (pin "19") (pinfunction "~{OE}_19") (pintype "input"))
      (node (ref "U4") (pin "1") (pinfunction "DIR_1") (pintype "input"))
      (node (ref "U4") (pin "10") (pinfunction "GND_10") (pintype "power_in"))
      (node (ref "U4") (pin "19") (pinfunction "~{OE}_19") (pintype "input"))
      (node (ref "U5") (pin "1") (pinfunction "DIR_1") (pintype "input"))
      (node (ref "U5") (pin "10") (pinfunction "GND_10") (pintype "power_in"))
      (node (ref "U5") (pin "19") (pinfunction "~{OE}_19") (pintype "input"))
      (node (ref "U6") (pin "1") (pinfunction "DIR_1") (pintype "input"))
      (node (ref "U6") (pin "10") (pinfunction "GND_10") (pintype "power_in"))
      (node (ref "U6") (pin "19") (pinfunction "~{OE}_19") (pintype "input"))
      (node (ref "U7") (pin "1") (pinfunction "DIR_1") (pintype "input"))
      (node (ref "U7") (pin "10") (pinfunction "GND_10") (pintype "power_in"))
      (node (ref "U7") (pin "19") (pinfunction "~{OE}_19") (pintype "input"))
      (node (ref "U8") (pin "1") (pinfunction "DIR_1") (pintype "input"))
      (node (ref "U8") (pin "10") (pinfunction "GND_10") (pintype "power_in"))
      (node (ref "U8") (pin "19") (pinfunction "~{OE}_19") (pintype "input"))
      (node (ref "U9") (pin "1") (pinfunction "DIR_1") (pintype "input"))
      (node (ref "U9") (pin "10") (pinfunction "GND_10") (pintype "power_in"))
      (node (ref "U9") (pin "19") (pinfunction "~{OE}_19") (pintype "input"))
    )
    (net (code "108") (name "unconnected-(U3-A8-Pad9)") (class "Default")
      (node (ref "U3") (pin "9") (pinfunction "A8_9") (pintype "bidirectional"))
    )
    (net (code "109") (name "unconnected-(U3-B8-Pad11)") (class "Default")
      (node (ref "U3") (pin "11") (pinfunction "B8_11") (pintype "bidirectional"))
    )
    (net (code "110") (name "unconnected-(U5-A8-Pad9)") (class "Default")
      (node (ref "U5") (pin "9") (pinfunction "A8_9") (pintype "bidirectional"))
    )
    (net (code "111") (name "unconnected-(U5-B8-Pad11)") (class "Default")
      (node (ref "U5") (pin "11") (pinfunction "B8_11") (pintype "bidirectional"))
    )
    (net (code "112") (name "unconnected-(U7-A8-Pad9)") (class "Default")
      (node (ref "U7") (pin "9") (pinfunction "A8_9") (pintype "bidirectional"))
    )
    (net (code "113") (name "unconnected-(U7-B8-Pad11)") (class "Default")
      (node (ref "U7") (pin "11") (pinfunction "B8_11") (pintype "bidirectional"))
    )
    (net (code "114") (name "unconnected-(U9-A8-Pad9)") (class "Default")
      (node (ref "U9") (pin "9") (pinfunction "A8_9") (pintype "bidirectional"))
    )
    (net (code "115") (name "unconnected-(U9-B8-Pad11)") (class "Default")
      (node (ref "U9") (pin "11") (pinfunction "B8_11") (pintype "bidirectional"))
    )
    (net (code "116") (name "unconnected-(U10-A7-Pad8)") (class "Default")
      (node (ref "U10") (pin "8") (pinfunction "A7_8") (pintype "bidirectional"))
    )
    (net (code "117") (name "unconnected-(U10-A8-Pad9)") (class "Default")
      (node (ref "U10") (pin "9") (pinfunction "A8_9") (pintype "bidirectional"))
    )
    (net (code "118") (name "unconnected-(U10-B7-Pad12)") (class "Default")
      (node (ref "U10") (pin "12") (pinfunction "B7_12") (pintype "bidirectional"))
    )
    (net (code "119") (name "unconnected-(U10-B8-Pad11)") (class "Default")
      (node (ref "U10") (pin "11") (pinfunction "B8_11") (pintype "bidirectional"))
    )
    (net (code "120") (name "unconnected-(U11-A8-Pad9)") (class "Default")
      (node (ref "U11") (pin "9") (pinfunction "A8_9") (pintype "bidirectional"))
    )
    (net (code "121") (name "unconnected-(U11-B8-Pad11)") (class "Default")
      (node (ref "U11") (pin "11") (pinfunction "B8_11") (pintype "bidirectional"))
    )
  )
)
